# RightSensor.net
KiCad netlist of a schematic drawn in EAGLE
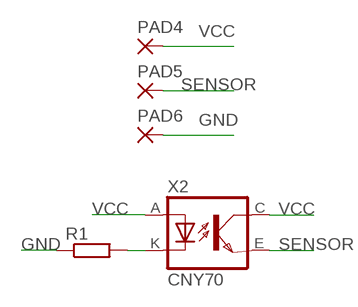
[diagram p0: schematic, sheet 1]

(export (version "E")
  (design (tool "Eeschema 10.0.6"))
  (components
    (comp (ref "PAD4")
      (value "WIREPADSMD1,27-254")
      (footprint "eagle-import:SMD1,27-2,54")
      (libsource (lib "eagle-import") (part "WIREPADSMD1,27-254"))
    )
    (comp (ref "PAD5")
      (value "WIREPADSMD1,27-254")
      (footprint "eagle-import:SMD1,27-2,54")
      (libsource (lib "eagle-import") (part "WIREPADSMD1,27-254"))
    )
    (comp (ref "PAD6")
      (value "WIREPADSMD1,27-254")
      (footprint "eagle-import:SMD1,27-2,54")
      (libsource (lib "eagle-import") (part "WIREPADSMD1,27-254"))
    )
    (comp (ref "R1")
      (value "RCL_R-EU_R0805")
      (footprint "eagle-import:RCL_R0805")
      (libsource (lib "eagle-import") (part "RCL_R-EU_R0805"))
    )
    (comp (ref "X2")
      (value "CNY70")
      (footprint "eagle-import:4")
      (libsource (lib "eagle-import") (part "CNY70"))
    )
  )
  (nets
    (net (code "1") (name "/GND") (class "Default")
      (node (ref "PAD6") (pin "1") (pinfunction "P_1") (pintype "passive"))
      (node (ref "R1") (pin "1") (pinfunction "1_1") (pintype "passive"))
    )
    (net (code "2") (name "/SENSOR") (class "Default")
      (node (ref "PAD5") (pin "1") (pinfunction "P_1") (pintype "passive"))
      (node (ref "X2") (pin "E") (pinfunction "EMI_E") (pintype "passive"))
    )
    (net (code "3") (name "/VCC") (class "Default")
      (node (ref "PAD4") (pin "1") (pinfunction "P_1") (pintype "passive"))
      (node (ref "X2") (pin "A") (pinfunction "A_A") (pintype "passive"))
      (node (ref "X2") (pin "C") (pinfunction "COL_C") (pintype "passive"))
    )
    (net (code "4") (name "Net-(X2-C)") (class "Default")
      (node (ref "R1") (pin "2") (pinfunction "2_2") (pintype "passive"))
      (node (ref "X2") (pin "K") (pinfunction "C_K") (pintype "passive"))
    )
  )
)
